# MicrocontrollerCircuitV2.net
KiCad netlist of a schematic drawn in EAGLE
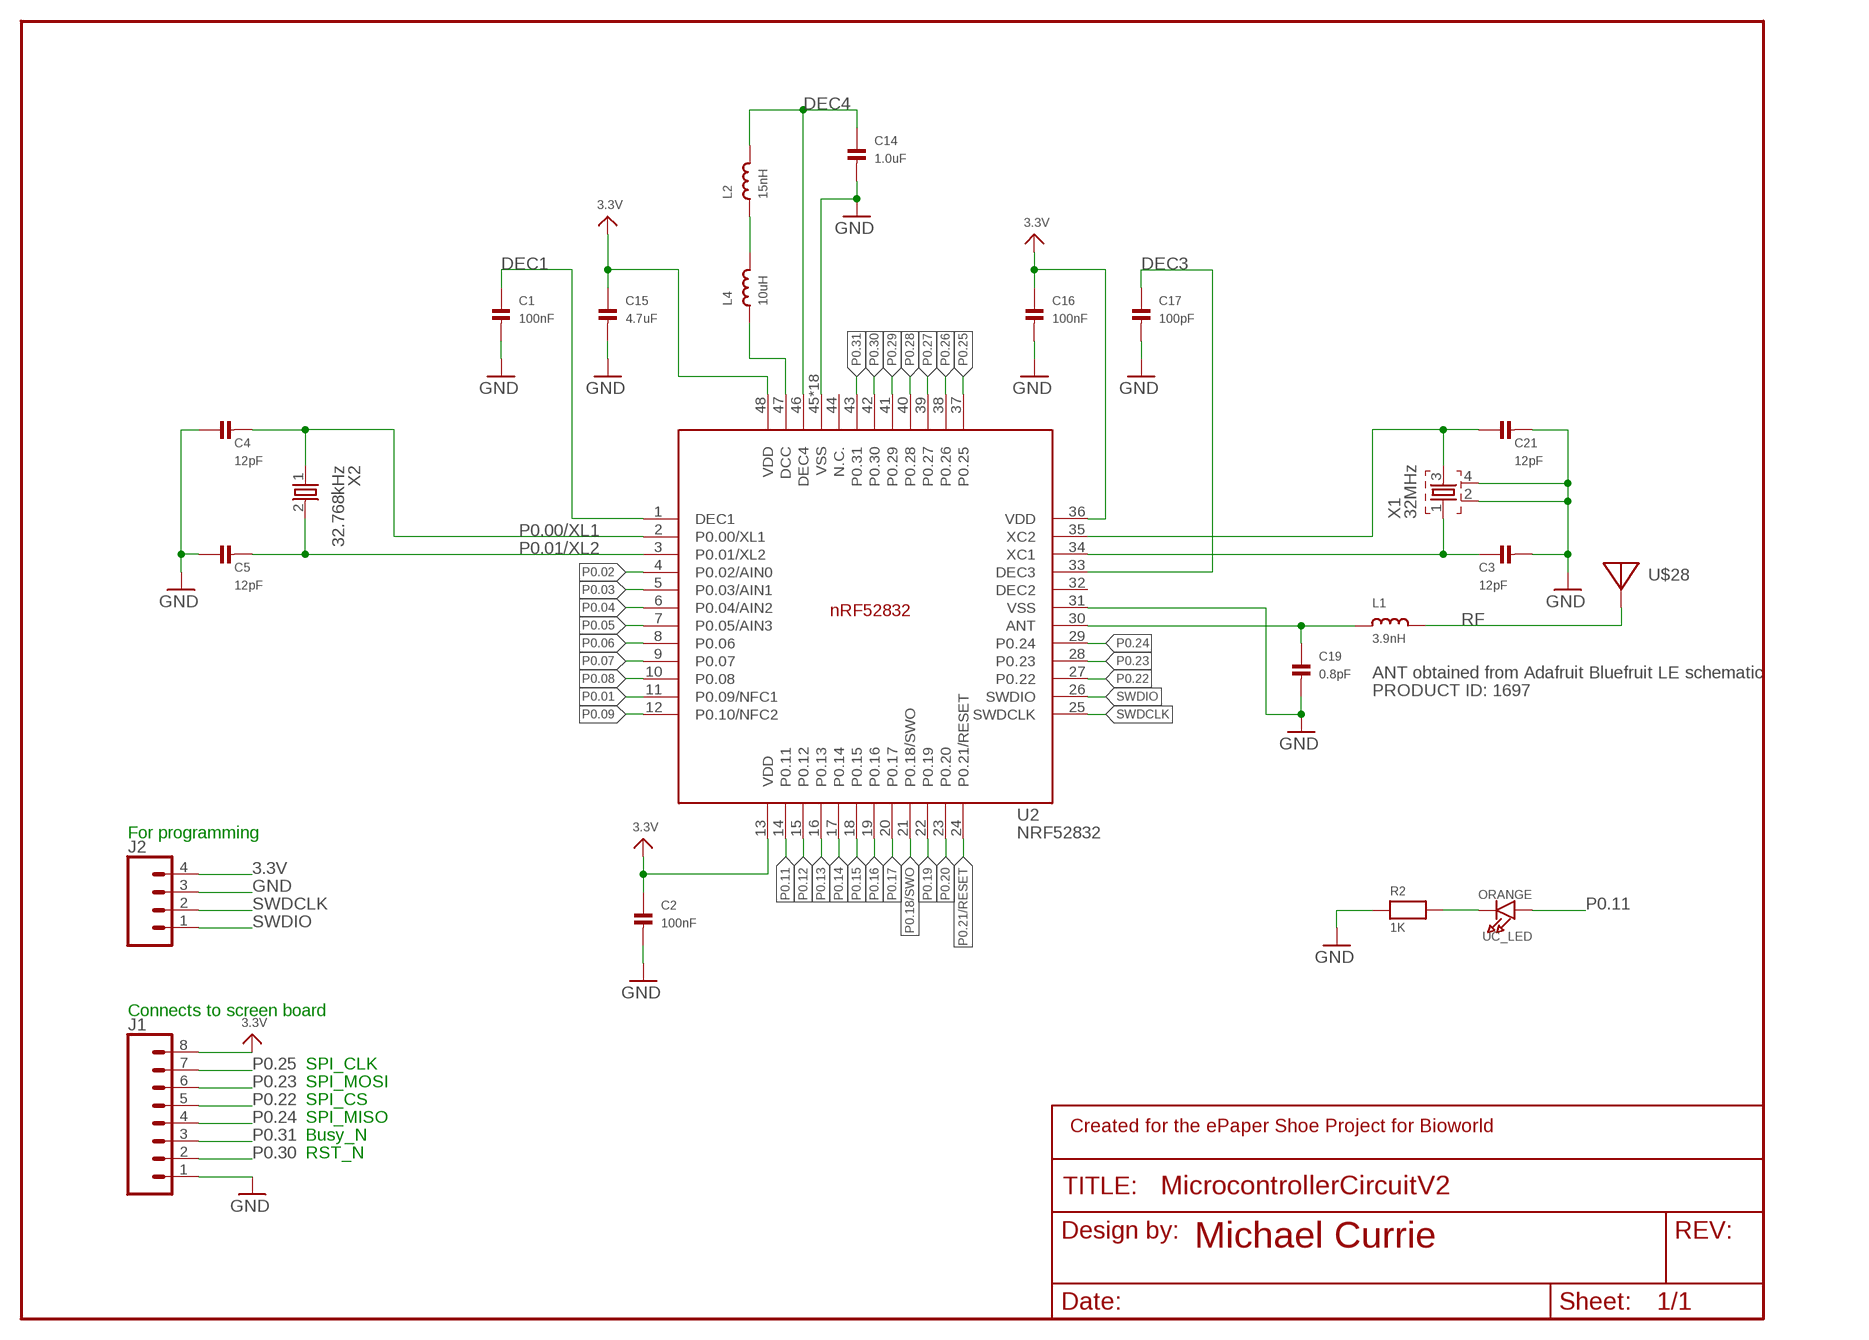
[diagram p0: schematic, sheet 1]

(export (version "E")
  (design (tool "Eeschema 10.0.6"))
  (components
    (comp (ref "C1")
      (value "100nF")
      (footprint "eagle-import:0805")
      (libsource (lib "eagle-import") (part "CAP_CERAMIC0805"))
    )
    (comp (ref "C2")
      (value "100nF")
      (footprint "eagle-import:0805")
      (libsource (lib "eagle-import") (part "CAP_CERAMIC0805"))
    )
    (comp (ref "C3")
      (value "12pF")
      (footprint "eagle-import:0805")
      (libsource (lib "eagle-import") (part "CAP_CERAMIC0805"))
    )
    (comp (ref "C4")
      (value "12pF")
      (footprint "eagle-import:0805")
      (libsource (lib "eagle-import") (part "CAP_CERAMIC0805"))
    )
    (comp (ref "C5")
      (value "12pF")
      (footprint "eagle-import:0805")
      (libsource (lib "eagle-import") (part "CAP_CERAMIC0805"))
    )
    (comp (ref "C14")
      (value "1.0uF")
      (footprint "eagle-import:0805")
      (libsource (lib "eagle-import") (part "CAP_CERAMIC0805"))
    )
    (comp (ref "C15")
      (value "4.7uF")
      (footprint "eagle-import:0805")
      (libsource (lib "eagle-import") (part "CAP_CERAMIC0805"))
    )
    (comp (ref "C16")
      (value "100nF")
      (footprint "eagle-import:0805")
      (libsource (lib "eagle-import") (part "CAP_CERAMIC0805"))
    )
    (comp (ref "C17")
      (value "100pF")
      (footprint "eagle-import:0805")
      (libsource (lib "eagle-import") (part "CAP_CERAMIC0805"))
    )
    (comp (ref "C19")
      (value "0.8pF")
      (footprint "eagle-import:0805")
      (libsource (lib "eagle-import") (part "CAP_CERAMIC0805"))
    )
    (comp (ref "C21")
      (value "12pF")
      (footprint "eagle-import:0805")
      (libsource (lib "eagle-import") (part "CAP_CERAMIC0805"))
    )
    (comp (ref "FRAME2")
      (value "FRAME-LETTER-MICHAELNO_PACKAGE")
      (footprint "eagle-import:DUMMY")
      (fields (field (name "DESIGNER") "Nobody"))
      (libsource (lib "eagle-import") (part "FRAME-LETTER-MICHAELNO_PACKAGE"))
    )
    (comp (ref "J1")
      (value "CONN_08\"")
      (footprint "eagle-import:1X08")
      (libsource (lib "eagle-import") (part "CONN_08{dblquote}"))
    )
    (comp (ref "J2")
      (value "CONN_04")
      (footprint "eagle-import:1X04")
      (libsource (lib "eagle-import") (part "CONN_04"))
    )
    (comp (ref "L1")
      (value "3.9nH")
      (footprint "eagle-import:0805")
      (libsource (lib "eagle-import") (part "INDUCTOR0805"))
    )
    (comp (ref "L2")
      (value "15nH")
      (footprint "eagle-import:0805")
      (libsource (lib "eagle-import") (part "INDUCTOR0805"))
    )
    (comp (ref "L4")
      (value "10uH")
      (footprint "eagle-import:0805")
      (libsource (lib "eagle-import") (part "INDUCTOR0805"))
    )
    (comp (ref "R2")
      (value "1K")
      (footprint "eagle-import:0805")
      (libsource (lib "eagle-import") (part "RESISTOR0805"))
    )
    (comp (ref "U$28")
      (value "ANTENNA_PCBNRF8001_1.6MM")
      (footprint "eagle-import:ANT_PCB_2.4GHZ_NRF8001_1.6MM_1OZ")
      (libsource (lib "eagle-import") (part "ANTENNA_PCBNRF8001_1.6MM"))
    )
    (comp (ref "U2")
      (value "NRF52832")
      (footprint "eagle-import:QFN40P600X600X90-48_N")
      (libsource (lib "eagle-import") (part "NRF52832"))
    )
    (comp (ref "UC_LED")
      (value "ORANGE")
      (footprint "eagle-import:CHIPLED_0805_NOOUTLINE")
      (libsource (lib "eagle-import") (part "LED0805_NOOUTLINE"))
    )
    (comp (ref "X1")
      (value "32MHz")
      (footprint "eagle-import:BT-XTAL_2016_N")
      (libsource (lib "eagle-import") (part "XTAL_32MHZ"))
    )
    (comp (ref "X2")
      (value "32.768kHz")
      (footprint "eagle-import:XTAL_3215_N")
      (libsource (lib "eagle-import") (part "XTAL_32KHZ"))
    )
  )
  (nets
    (net (code "1") (name "/DEC1") (class "Default")
      (node (ref "C1") (pin "1") (pinfunction "P$1_1") (pintype "passive"))
      (node (ref "U2") (pin "1") (pinfunction "DEC1_1") (pintype "power_in"))
    )
    (net (code "2") (name "/DEC3") (class "Default")
      (node (ref "C17") (pin "1") (pinfunction "P$1_1") (pintype "passive"))
      (node (ref "U2") (pin "33") (pinfunction "DEC3_33") (pintype "bidirectional"))
    )
    (net (code "3") (name "/DEC4") (class "Default")
      (node (ref "C14") (pin "1") (pinfunction "P$1_1") (pintype "passive"))
      (node (ref "L2") (pin "2") (pinfunction "2_2") (pintype "passive"))
      (node (ref "U2") (pin "46") (pinfunction "DEC4_46") (pintype "power_in"))
    )
    (net (code "4") (name "/P0.00{slash}XL1") (class "Default")
      (node (ref "C4") (pin "2") (pinfunction "P$2_2") (pintype "passive"))
      (node (ref "U2") (pin "2") (pinfunction "P0.00/XL1_2") (pintype "bidirectional"))
      (node (ref "X2") (pin "1") (pinfunction "1_1") (pintype "passive"))
    )
    (net (code "5") (name "/P0.01{slash}XL2") (class "Default")
      (node (ref "C5") (pin "2") (pinfunction "P$2_2") (pintype "passive"))
      (node (ref "U2") (pin "3") (pinfunction "P0.01/XL2_3") (pintype "bidirectional"))
      (node (ref "X2") (pin "2") (pinfunction "2_2") (pintype "passive"))
    )
    (net (code "6") (name "/RF") (class "Default")
      (node (ref "L1") (pin "2") (pinfunction "2_2") (pintype "passive"))
      (node (ref "U$28") (pin "FEED") (pinfunction "P$1_FEED") (pintype "passive"))
    )
    (net (code "7") (name "3.3V") (class "Default")
      (node (ref "C15") (pin "1") (pinfunction "P$1_1") (pintype "passive"))
      (node (ref "C16") (pin "1") (pinfunction "P$1_1") (pintype "passive"))
      (node (ref "C2") (pin "1") (pinfunction "P$1_1") (pintype "passive"))
      (node (ref "J1") (pin "8") (pinfunction "8_8") (pintype "passive"))
      (node (ref "J2") (pin "4") (pinfunction "4_4") (pintype "passive"))
      (node (ref "U2") (pin "13") (pinfunction "VDD_13") (pintype "power_in"))
      (node (ref "U2") (pin "36") (pinfunction "VDD_36") (pintype "power_in"))
      (node (ref "U2") (pin "48") (pinfunction "VDD_48") (pintype "power_in"))
    )
    (net (code "8") (name "GND") (class "Default")
      (node (ref "C1") (pin "2") (pinfunction "P$2_2") (pintype "passive"))
      (node (ref "C14") (pin "2") (pinfunction "P$2_2") (pintype "passive"))
      (node (ref "C15") (pin "2") (pinfunction "P$2_2") (pintype "passive"))
      (node (ref "C16") (pin "2") (pinfunction "P$2_2") (pintype "passive"))
      (node (ref "C17") (pin "2") (pinfunction "P$2_2") (pintype "passive"))
      (node (ref "C19") (pin "2") (pinfunction "P$2_2") (pintype "passive"))
      (node (ref "C2") (pin "2") (pinfunction "P$2_2") (pintype "passive"))
      (node (ref "C21") (pin "2") (pinfunction "P$2_2") (pintype "passive"))
      (node (ref "C3") (pin "2") (pinfunction "P$2_2") (pintype "passive"))
      (node (ref "C4") (pin "1") (pinfunction "P$1_1") (pintype "passive"))
      (node (ref "C5") (pin "1") (pinfunction "P$1_1") (pintype "passive"))
      (node (ref "J1") (pin "1") (pinfunction "1_1") (pintype "passive"))
      (node (ref "J2") (pin "3") (pinfunction "3_3") (pintype "passive"))
      (node (ref "R2") (pin "1") (pinfunction "1_1") (pintype "passive"))
      (node (ref "U2") (pin "31") (pinfunction "VSS_31") (pintype "bidirectional"))
      (node (ref "U2") (pin "45") (pinfunction "VSS_45") (pintype "power_in"))
      (node (ref "U2") (pin "PAD") (pinfunction "VSS_PAD") (pintype "power_in"))
      (node (ref "U2") (pin "PAD@VIA01") (pinfunction "VSS_PAD@VIA01") (pintype "power_in"))
      (node (ref "U2") (pin "PAD@VIA02") (pinfunction "VSS_PAD@VIA02") (pintype "power_in"))
      (node (ref "U2") (pin "PAD@VIA03") (pinfunction "VSS_PAD@VIA03") (pintype "power_in"))
      (node (ref "U2") (pin "PAD@VIA04") (pinfunction "VSS_PAD@VIA04") (pintype "power_in"))
      (node (ref "U2") (pin "PAD@VIA05") (pinfunction "VSS_PAD@VIA05") (pintype "power_in"))
      (node (ref "U2") (pin "PAD@VIA06") (pinfunction "VSS_PAD@VIA06") (pintype "power_in"))
      (node (ref "U2") (pin "PAD@VIA07") (pinfunction "VSS_PAD@VIA07") (pintype "power_in"))
      (node (ref "U2") (pin "PAD@VIA08") (pinfunction "VSS_PAD@VIA08") (pintype "power_in"))
      (node (ref "U2") (pin "PAD@VIA09") (pinfunction "VSS_PAD@VIA09") (pintype "power_in"))
      (node (ref "U2") (pin "PAD@VIA10") (pinfunction "VSS_PAD@VIA10") (pintype "power_in"))
      (node (ref "U2") (pin "PAD@VIA11") (pinfunction "VSS_PAD@VIA11") (pintype "power_in"))
      (node (ref "U2") (pin "PAD@VIA12") (pinfunction "VSS_PAD@VIA12") (pintype "power_in"))
      (node (ref "U2") (pin "PAD@VIA13") (pinfunction "VSS_PAD@VIA13") (pintype "power_in"))
      (node (ref "U2") (pin "PAD@VIA14") (pinfunction "VSS_PAD@VIA14") (pintype "power_in"))
      (node (ref "U2") (pin "PAD@VIA15") (pinfunction "VSS_PAD@VIA15") (pintype "power_in"))
      (node (ref "U2") (pin "PAD@VIA16") (pinfunction "VSS_PAD@VIA16") (pintype "power_in"))
      (node (ref "X1") (pin "2") (pinfunction "2_2") (pintype "passive"))
      (node (ref "X1") (pin "4") (pinfunction "4_4") (pintype "passive"))
    )
    (net (code "9") (name "Net-(C3-P$1)") (class "Default")
      (node (ref "C3") (pin "1") (pinfunction "P$1_1") (pintype "passive"))
      (node (ref "U2") (pin "34") (pinfunction "XC1_34") (pintype "input"))
      (node (ref "X1") (pin "1") (pinfunction "1_1") (pintype "passive"))
    )
    (net (code "10") (name "Net-(C19-P$1)") (class "Default")
      (node (ref "C19") (pin "1") (pinfunction "P$1_1") (pintype "passive"))
      (node (ref "L1") (pin "1") (pinfunction "1_1") (pintype "passive"))
      (node (ref "U2") (pin "30") (pinfunction "ANT_30") (pintype "bidirectional"))
    )
    (net (code "11") (name "Net-(C21-P$1)") (class "Default")
      (node (ref "C21") (pin "1") (pinfunction "P$1_1") (pintype "passive"))
      (node (ref "U2") (pin "35") (pinfunction "XC2_35") (pintype "output"))
      (node (ref "X1") (pin "3") (pinfunction "3_3") (pintype "passive"))
    )
    (net (code "12") (name "Net-(L2-Pad1)") (class "Default")
      (node (ref "L2") (pin "1") (pinfunction "1_1") (pintype "passive"))
      (node (ref "L4") (pin "2") (pinfunction "2_2") (pintype "passive"))
    )
    (net (code "13") (name "Net-(R2-Pad2)") (class "Default")
      (node (ref "R2") (pin "2") (pinfunction "2_2") (pintype "passive"))
      (node (ref "UC_LED") (pin "C") (pinfunction "C_C") (pintype "passive"))
    )
    (net (code "14") (name "Net-(U2-DCC)") (class "Default")
      (node (ref "L4") (pin "1") (pinfunction "1_1") (pintype "passive"))
      (node (ref "U2") (pin "47") (pinfunction "DCC_47") (pintype "output"))
    )
    (net (code "15") (name "P0.01") (class "Default")
      (node (ref "U2") (pin "11") (pinfunction "P0.09/NFC1_11") (pintype "bidirectional"))
    )
    (net (code "16") (name "P0.02") (class "Default")
      (node (ref "U2") (pin "4") (pinfunction "P0.02/AIN0_4") (pintype "bidirectional"))
    )
    (net (code "17") (name "P0.03") (class "Default")
      (node (ref "U2") (pin "5") (pinfunction "P0.03/AIN1_5") (pintype "bidirectional"))
    )
    (net (code "18") (name "P0.04") (class "Default")
      (node (ref "U2") (pin "6") (pinfunction "P0.04/AIN2_6") (pintype "bidirectional"))
    )
    (net (code "19") (name "P0.05") (class "Default")
      (node (ref "U2") (pin "7") (pinfunction "P0.05/AIN3_7") (pintype "bidirectional"))
    )
    (net (code "20") (name "P0.06") (class "Default")
      (node (ref "U2") (pin "8") (pinfunction "P0.06_8") (pintype "bidirectional"))
    )
    (net (code "21") (name "P0.07") (class "Default")
      (node (ref "U2") (pin "9") (pinfunction "P0.07_9") (pintype "bidirectional"))
    )
    (net (code "22") (name "P0.08") (class "Default")
      (node (ref "U2") (pin "10") (pinfunction "P0.08_10") (pintype "bidirectional"))
    )
    (net (code "23") (name "P0.09") (class "Default")
      (node (ref "U2") (pin "12") (pinfunction "P0.10/NFC2_12") (pintype "bidirectional"))
    )
    (net (code "24") (name "P0.11") (class "Default")
      (node (ref "U2") (pin "14") (pinfunction "P0.11_14") (pintype "bidirectional"))
      (node (ref "UC_LED") (pin "A") (pinfunction "A_A") (pintype "passive"))
    )
    (net (code "25") (name "P0.12") (class "Default")
      (node (ref "U2") (pin "15") (pinfunction "P0.12_15") (pintype "bidirectional"))
    )
    (net (code "26") (name "P0.13") (class "Default")
      (node (ref "U2") (pin "16") (pinfunction "P0.13_16") (pintype "bidirectional"))
    )
    (net (code "27") (name "P0.14") (class "Default")
      (node (ref "U2") (pin "17") (pinfunction "P0.14_17") (pintype "bidirectional"))
    )
    (net (code "28") (name "P0.15") (class "Default")
      (node (ref "U2") (pin "18") (pinfunction "P0.15_18") (pintype "bidirectional"))
    )
    (net (code "29") (name "P0.16") (class "Default")
      (node (ref "U2") (pin "19") (pinfunction "P0.16_19") (pintype "bidirectional"))
    )
    (net (code "30") (name "P0.17") (class "Default")
      (node (ref "U2") (pin "20") (pinfunction "P0.17_20") (pintype "bidirectional"))
    )
    (net (code "31") (name "P0.18{slash}SWO") (class "Default")
      (node (ref "U2") (pin "21") (pinfunction "P0.18/SWO_21") (pintype "bidirectional"))
    )
    (net (code "32") (name "P0.19") (class "Default")
      (node (ref "U2") (pin "22") (pinfunction "P0.19_22") (pintype "bidirectional"))
    )
    (net (code "33") (name "P0.20") (class "Default")
      (node (ref "U2") (pin "23") (pinfunction "P0.20_23") (pintype "bidirectional"))
    )
    (net (code "34") (name "P0.21{slash}RESET") (class "Default")
      (node (ref "U2") (pin "24") (pinfunction "P0.21/RESET_24") (pintype "bidirectional"))
    )
    (net (code "35") (name "P0.22") (class "Default")
      (node (ref "J1") (pin "5") (pinfunction "5_5") (pintype "passive"))
      (node (ref "U2") (pin "27") (pinfunction "P0.22_27") (pintype "bidirectional"))
    )
    (net (code "36") (name "P0.23") (class "Default")
      (node (ref "J1") (pin "6") (pinfunction "6_6") (pintype "passive"))
      (node (ref "U2") (pin "28") (pinfunction "P0.23_28") (pintype "bidirectional"))
    )
    (net (code "37") (name "P0.24") (class "Default")
      (node (ref "J1") (pin "4") (pinfunction "4_4") (pintype "passive"))
      (node (ref "U2") (pin "29") (pinfunction "P0.24_29") (pintype "bidirectional"))
    )
    (net (code "38") (name "P0.25") (class "Default")
      (node (ref "J1") (pin "7") (pinfunction "7_7") (pintype "passive"))
      (node (ref "U2") (pin "37") (pinfunction "P0.25_37") (pintype "bidirectional"))
    )
    (net (code "39") (name "P0.26") (class "Default")
      (node (ref "U2") (pin "38") (pinfunction "P0.26_38") (pintype "bidirectional"))
    )
    (net (code "40") (name "P0.27") (class "Default")
      (node (ref "U2") (pin "39") (pinfunction "P0.27_39") (pintype "bidirectional"))
    )
    (net (code "41") (name "P0.28") (class "Default")
      (node (ref "U2") (pin "40") (pinfunction "P0.28_40") (pintype "bidirectional"))
    )
    (net (code "42") (name "P0.29") (class "Default")
      (node (ref "U2") (pin "41") (pinfunction "P0.29_41") (pintype "bidirectional"))
    )
    (net (code "43") (name "P0.30") (class "Default")
      (node (ref "J1") (pin "2") (pinfunction "2_2") (pintype "passive"))
      (node (ref "U2") (pin "42") (pinfunction "P0.30_42") (pintype "bidirectional"))
    )
    (net (code "44") (name "P0.31") (class "Default")
      (node (ref "J1") (pin "3") (pinfunction "3_3") (pintype "passive"))
      (node (ref "U2") (pin "43") (pinfunction "P0.31_43") (pintype "bidirectional"))
    )
    (net (code "45") (name "SWDCLK") (class "Default")
      (node (ref "J2") (pin "2") (pinfunction "2_2") (pintype "passive"))
      (node (ref "U2") (pin "25") (pinfunction "SWDCLK_25") (pintype "input"))
    )
    (net (code "46") (name "SWDIO") (class "Default")
      (node (ref "J2") (pin "1") (pinfunction "1_1") (pintype "passive"))
      (node (ref "U2") (pin "26") (pinfunction "SWDIO_26") (pintype "bidirectional"))
    )
    (net (code "47") (name "unconnected-(U2-DEC2-Pad32)") (class "Default")
      (node (ref "U2") (pin "32") (pinfunction "DEC2_32") (pintype "bidirectional"))
    )
    (net (code "48") (name "unconnected-(U2-N.C.-Pad44)") (class "Default")
      (node (ref "U2") (pin "44") (pinfunction "N.C._44") (pintype "no_connect"))
    )
  )
)
